# eeZeePower.net
KiCad netlist of a schematic drawn in EAGLE
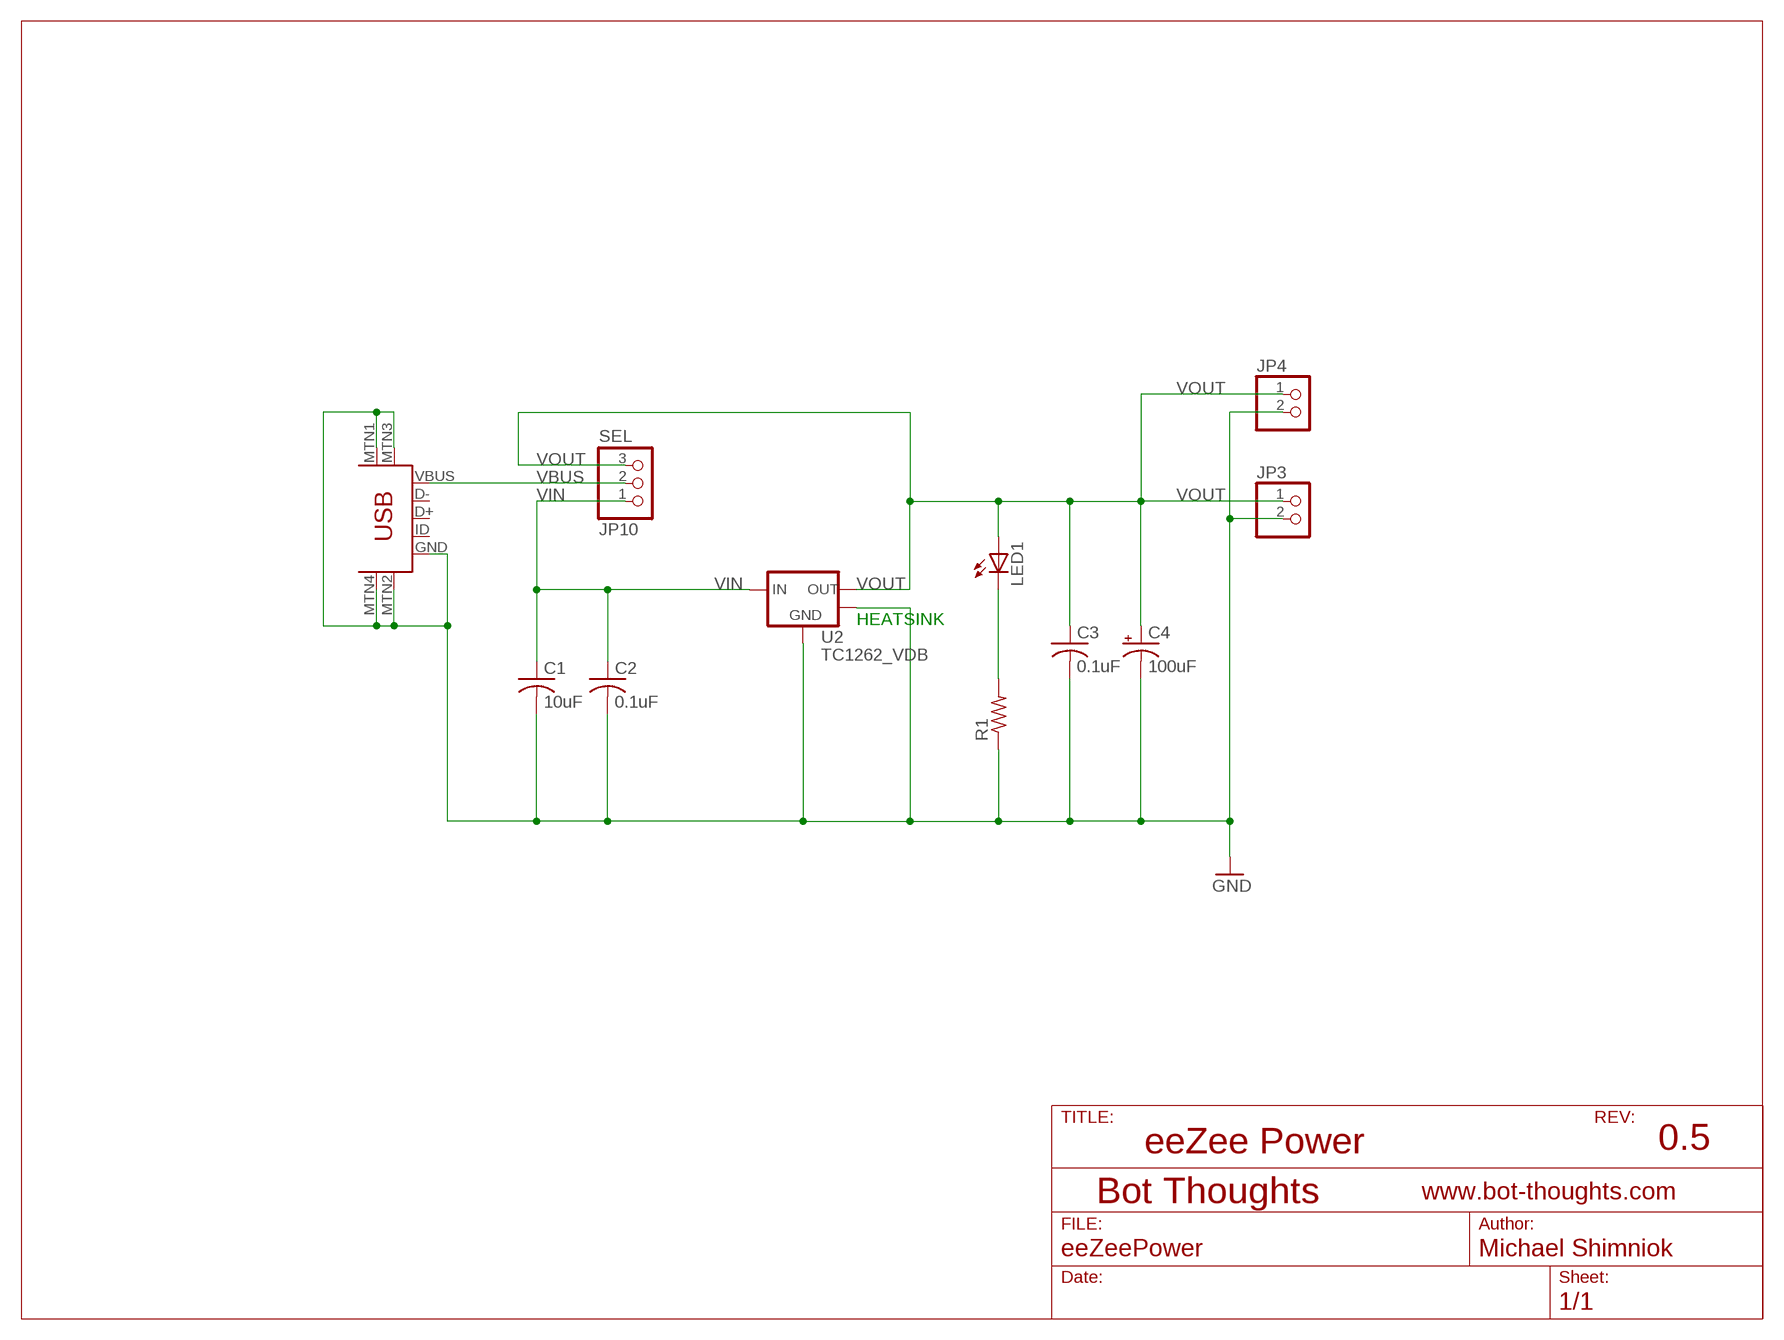
[diagram p0: schematic, sheet 1]

(export (version "E")
  (design (tool "Eeschema 10.0.6"))
  (components
    (comp (ref "C1")
      (value "10uF")
      (footprint "eagle-import:C1206")
      (libsource (lib "eagle-import") (part "C-USC1206"))
    )
    (comp (ref "C2")
      (value "0.1uF")
      (footprint "eagle-import:C0603")
      (libsource (lib "eagle-import") (part "C-USC0603"))
    )
    (comp (ref "C3")
      (value "0.1uF")
      (footprint "eagle-import:C0603")
      (libsource (lib "eagle-import") (part "C-USC0603"))
    )
    (comp (ref "C4")
      (value "100uF")
      (footprint "eagle-import:SMC_B")
      (libsource (lib "eagle-import") (part "CPOL-USSMCB"))
    )
    (comp (ref "JP3")
      (value "PINHD-1X02_2.54-S")
      (footprint "eagle-import:1X02-S")
      (libsource (lib "eagle-import") (part "PINHD-1X02_2.54-S"))
    )
    (comp (ref "JP4")
      (value "PINHD-1X02_2.54-S")
      (footprint "eagle-import:1X02-S")
      (libsource (lib "eagle-import") (part "PINHD-1X02_2.54-S"))
    )
    (comp (ref "JP10")
      (value "SEL")
      (footprint "eagle-import:1X03-S")
      (libsource (lib "eagle-import") (part "PINHD-1X03_2.54-S"))
    )
    (comp (ref "LED1")
      (value "LEDCHIPLED_1206")
      (footprint "eagle-import:CHIPLED_1206")
      (libsource (lib "eagle-import") (part "LEDCHIPLED_1206"))
    )
    (comp (ref "R1")
      (value "R-US_R0603")
      (footprint "eagle-import:R0603")
      (libsource (lib "eagle-import") (part "R-US_R0603"))
    )
    (comp (ref "U$1")
      (value "USB-MINIB-5PIN")
      (footprint "eagle-import:USB-MINIB")
      (libsource (lib "eagle-import") (part "USB-MINIB-5PIN"))
    )
    (comp (ref "U2")
      (value "TC1262_VDB")
      (footprint "eagle-import:SOT-223-3")
      (libsource (lib "eagle-import") (part "TC1262_VDB"))
    )
  )
  (nets
    (net (code "1") (name "/VBUS") (class "Default")
      (node (ref "JP10") (pin "2") (pinfunction "2_2") (pintype "passive"))
      (node (ref "U$1") (pin "VBUS") (pinfunction "VBUS_VBUS") (pintype "bidirectional"))
    )
    (net (code "2") (name "/VIN") (class "Default")
      (node (ref "C1") (pin "1") (pinfunction "1_1") (pintype "passive"))
      (node (ref "C2") (pin "1") (pinfunction "1_1") (pintype "passive"))
      (node (ref "JP10") (pin "1") (pinfunction "1_1") (pintype "passive"))
      (node (ref "U2") (pin "1") (pinfunction "VIN_1") (pintype "bidirectional"))
    )
    (net (code "3") (name "/VOUT") (class "Default")
      (node (ref "C3") (pin "1") (pinfunction "1_1") (pintype "passive"))
      (node (ref "C4") (pin "+") (pinfunction "+_+") (pintype "passive"))
      (node (ref "JP10") (pin "3") (pinfunction "3_3") (pintype "passive"))
      (node (ref "JP3") (pin "1") (pinfunction "1_1") (pintype "passive"))
      (node (ref "JP4") (pin "1") (pinfunction "1_1") (pintype "passive"))
      (node (ref "LED1") (pin "A") (pinfunction "A_A") (pintype "passive"))
      (node (ref "U2") (pin "3") (pinfunction "VOUT_3") (pintype "bidirectional"))
    )
    (net (code "4") (name "GND") (class "Default")
      (node (ref "C1") (pin "2") (pinfunction "2_2") (pintype "passive"))
      (node (ref "C2") (pin "2") (pinfunction "2_2") (pintype "passive"))
      (node (ref "C3") (pin "2") (pinfunction "2_2") (pintype "passive"))
      (node (ref "C4") (pin "-") (pinfunction "-_-") (pintype "passive"))
      (node (ref "JP3") (pin "2") (pinfunction "2_2") (pintype "passive"))
      (node (ref "JP4") (pin "2") (pinfunction "2_2") (pintype "passive"))
      (node (ref "R1") (pin "1") (pinfunction "1_1") (pintype "passive"))
      (node (ref "U$1") (pin "GND") (pinfunction "GND_GND") (pintype "bidirectional"))
      (node (ref "U$1") (pin "MTN1") (pinfunction "MTN2_MTN1") (pintype "bidirectional"))
      (node (ref "U$1") (pin "MTN2") (pinfunction "MTN3_MTN2") (pintype "bidirectional"))
      (node (ref "U$1") (pin "MTN3") (pinfunction "MTN1_MTN3") (pintype "bidirectional"))
      (node (ref "U$1") (pin "MTN4") (pinfunction "MTN4_MTN4") (pintype "bidirectional"))
      (node (ref "U2") (pin "2") (pinfunction "GND_2") (pintype "bidirectional"))
      (node (ref "U2") (pin "4") (pinfunction "TAB_4") (pintype "bidirectional"))
    )
    (net (code "5") (name "Net-(LED1-PadC)") (class "Default")
      (node (ref "LED1") (pin "C") (pinfunction "C_C") (pintype "passive"))
      (node (ref "R1") (pin "2") (pinfunction "2_2") (pintype "passive"))
    )
    (net (code "6") (name "unconnected-(U$1-PadD+)") (class "Default")
      (node (ref "U$1") (pin "D+") (pinfunction "D+_D+") (pintype "bidirectional"))
    )
    (net (code "7") (name "unconnected-(U$1-PadD-)") (class "Default")
      (node (ref "U$1") (pin "D-") (pinfunction "D-_D-") (pintype "bidirectional"))
    )
    (net (code "8") (name "unconnected-(U$1-PadID)") (class "Default")
      (node (ref "U$1") (pin "ID") (pinfunction "ID_ID") (pintype "bidirectional"))
    )
  )
)
